# module_SX1278_A.net
KiCad netlist of a schematic drawn in EAGLE
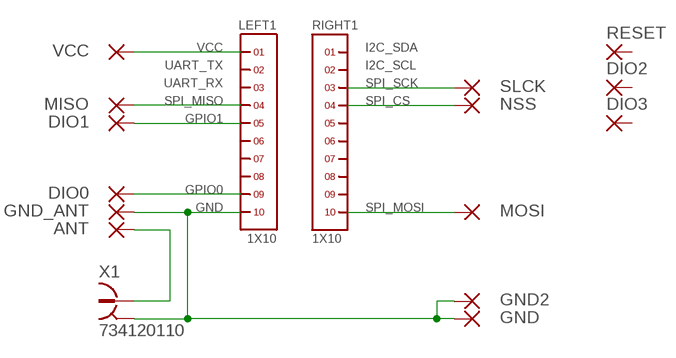
[diagram p0: schematic, sheet 1]

(export (version "E")
  (design (tool "Eeschema 10.0.6"))
  (components
    (comp (ref "ANT")
      (value "SMD1")
      (footprint "eagle-import:SMD0,65-1,27")
      (libsource (lib "eagle-import") (part "SMD1"))
    )
    (comp (ref "DIO0")
      (value "SMD1")
      (footprint "eagle-import:SMD0,65-1,27")
      (libsource (lib "eagle-import") (part "SMD1"))
    )
    (comp (ref "DIO1")
      (value "SMD1")
      (footprint "eagle-import:SMD0,65-1,27")
      (libsource (lib "eagle-import") (part "SMD1"))
    )
    (comp (ref "DIO2")
      (value "SMD1")
      (footprint "eagle-import:SMD0,65-1,27")
      (libsource (lib "eagle-import") (part "SMD1"))
    )
    (comp (ref "DIO3")
      (value "SMD1")
      (footprint "eagle-import:SMD0,65-1,27")
      (libsource (lib "eagle-import") (part "SMD1"))
    )
    (comp (ref "GND")
      (value "SMD1")
      (footprint "eagle-import:SMD0,65-1,27")
      (libsource (lib "eagle-import") (part "SMD1"))
    )
    (comp (ref "GND2")
      (value "SMD1")
      (footprint "eagle-import:SMD0,65-1,27")
      (libsource (lib "eagle-import") (part "SMD1"))
    )
    (comp (ref "GND_ANT")
      (value "SMD1")
      (footprint "eagle-import:SMD0,65-1,27")
      (libsource (lib "eagle-import") (part "SMD1"))
    )
    (comp (ref "LEFT1")
      (value "1X10")
      (footprint "eagle-import:1X10")
      (libsource (lib "eagle-import") (part "1X10"))
    )
    (comp (ref "MISO")
      (value "SMD1")
      (footprint "eagle-import:SMD0,65-1,27")
      (libsource (lib "eagle-import") (part "SMD1"))
    )
    (comp (ref "MOSI")
      (value "SMD1")
      (footprint "eagle-import:SMD0,65-1,27")
      (libsource (lib "eagle-import") (part "SMD1"))
    )
    (comp (ref "NSS")
      (value "SMD1")
      (footprint "eagle-import:SMD0,65-1,27")
      (libsource (lib "eagle-import") (part "SMD1"))
    )
    (comp (ref "RESET")
      (value "SMD1")
      (footprint "eagle-import:SMD0,65-1,27")
      (libsource (lib "eagle-import") (part "SMD1"))
    )
    (comp (ref "RIGHT1")
      (value "1X10")
      (footprint "eagle-import:1X10")
      (libsource (lib "eagle-import") (part "1X10"))
    )
    (comp (ref "SLCK")
      (value "SMD1")
      (footprint "eagle-import:SMD0,65-1,27")
      (libsource (lib "eagle-import") (part "SMD1"))
    )
    (comp (ref "VCC")
      (value "SMD1")
      (footprint "eagle-import:SMD0,65-1,27")
      (libsource (lib "eagle-import") (part "SMD1"))
    )
    (comp (ref "X1")
      (value "734120110")
      (footprint "eagle-import:734120110")
      (libsource (lib "eagle-import") (part "734120110"))
    )
  )
  (nets
    (net (code "1") (name "Net-(ANT-P)") (class "Default")
      (node (ref "ANT") (pin "1") (pinfunction "P_1") (pintype "passive"))
      (node (ref "X1") (pin "1") (pinfunction "1_1") (pintype "passive"))
    )
    (net (code "2") (name "Net-(DIO0-P)") (class "Default")
      (node (ref "DIO0") (pin "1") (pinfunction "P_1") (pintype "passive"))
      (node (ref "LEFT1") (pin "9") (pinfunction "9_9") (pintype "bidirectional"))
    )
    (net (code "3") (name "Net-(DIO1-P)") (class "Default")
      (node (ref "DIO1") (pin "1") (pinfunction "P_1") (pintype "passive"))
      (node (ref "LEFT1") (pin "5") (pinfunction "5_5") (pintype "bidirectional"))
    )
    (net (code "4") (name "Net-(GND-P)") (class "Default")
      (node (ref "GND") (pin "1") (pinfunction "P_1") (pintype "passive"))
      (node (ref "GND2") (pin "1") (pinfunction "P_1") (pintype "passive"))
      (node (ref "GND_ANT") (pin "1") (pinfunction "P_1") (pintype "passive"))
      (node (ref "LEFT1") (pin "10") (pinfunction "10_10") (pintype "bidirectional"))
      (node (ref "X1") (pin "S@1") (pinfunction "2_S@1") (pintype "passive"))
      (node (ref "X1") (pin "S@2") (pinfunction "2_S@2") (pintype "passive"))
      (node (ref "X1") (pin "S@3") (pinfunction "2_S@3") (pintype "passive"))
    )
    (net (code "5") (name "Net-(MISO-P)") (class "Default")
      (node (ref "LEFT1") (pin "4") (pinfunction "4_4") (pintype "bidirectional"))
      (node (ref "MISO") (pin "1") (pinfunction "P_1") (pintype "passive"))
    )
    (net (code "6") (name "Net-(MOSI-P)") (class "Default")
      (node (ref "MOSI") (pin "1") (pinfunction "P_1") (pintype "passive"))
      (node (ref "RIGHT1") (pin "10") (pinfunction "10_10") (pintype "bidirectional"))
    )
    (net (code "7") (name "Net-(NSS-P)") (class "Default")
      (node (ref "NSS") (pin "1") (pinfunction "P_1") (pintype "passive"))
      (node (ref "RIGHT1") (pin "4") (pinfunction "4_4") (pintype "bidirectional"))
    )
    (net (code "8") (name "Net-(SLCK-P)") (class "Default")
      (node (ref "RIGHT1") (pin "3") (pinfunction "3_3") (pintype "bidirectional"))
      (node (ref "SLCK") (pin "1") (pinfunction "P_1") (pintype "passive"))
    )
    (net (code "9") (name "Net-(VCC-P)") (class "Default")
      (node (ref "LEFT1") (pin "1") (pinfunction "1_1") (pintype "bidirectional"))
      (node (ref "VCC") (pin "1") (pinfunction "P_1") (pintype "passive"))
    )
    (net (code "10") (name "unconnected-(DIO2-P-Pad1)") (class "Default")
      (node (ref "DIO2") (pin "1") (pinfunction "P_1") (pintype "passive"))
    )
    (net (code "11") (name "unconnected-(DIO3-P-Pad1)") (class "Default")
      (node (ref "DIO3") (pin "1") (pinfunction "P_1") (pintype "passive"))
    )
    (net (code "12") (name "unconnected-(LEFT1-Pad2)") (class "Default")
      (node (ref "LEFT1") (pin "2") (pinfunction "2_2") (pintype "bidirectional"))
    )
    (net (code "13") (name "unconnected-(LEFT1-Pad3)") (class "Default")
      (node (ref "LEFT1") (pin "3") (pinfunction "3_3") (pintype "bidirectional"))
    )
    (net (code "14") (name "unconnected-(LEFT1-Pad6)") (class "Default")
      (node (ref "LEFT1") (pin "6") (pinfunction "6_6") (pintype "bidirectional"))
    )
    (net (code "15") (name "unconnected-(LEFT1-Pad7)") (class "Default")
      (node (ref "LEFT1") (pin "7") (pinfunction "7_7") (pintype "bidirectional"))
    )
    (net (code "16") (name "unconnected-(LEFT1-Pad8)") (class "Default")
      (node (ref "LEFT1") (pin "8") (pinfunction "8_8") (pintype "bidirectional"))
    )
    (net (code "17") (name "unconnected-(RESET-P-Pad1)") (class "Default")
      (node (ref "RESET") (pin "1") (pinfunction "P_1") (pintype "passive"))
    )
    (net (code "18") (name "unconnected-(RIGHT1-Pad1)") (class "Default")
      (node (ref "RIGHT1") (pin "1") (pinfunction "1_1") (pintype "bidirectional"))
    )
    (net (code "19") (name "unconnected-(RIGHT1-Pad2)") (class "Default")
      (node (ref "RIGHT1") (pin "2") (pinfunction "2_2") (pintype "bidirectional"))
    )
    (net (code "20") (name "unconnected-(RIGHT1-Pad5)") (class "Default")
      (node (ref "RIGHT1") (pin "5") (pinfunction "5_5") (pintype "bidirectional"))
    )
    (net (code "21") (name "unconnected-(RIGHT1-Pad6)") (class "Default")
      (node (ref "RIGHT1") (pin "6") (pinfunction "6_6") (pintype "bidirectional"))
    )
    (net (code "22") (name "unconnected-(RIGHT1-Pad7)") (class "Default")
      (node (ref "RIGHT1") (pin "7") (pinfunction "7_7") (pintype "bidirectional"))
    )
    (net (code "23") (name "unconnected-(RIGHT1-Pad8)") (class "Default")
      (node (ref "RIGHT1") (pin "8") (pinfunction "8_8") (pintype "bidirectional"))
    )
    (net (code "24") (name "unconnected-(RIGHT1-Pad9)") (class "Default")
      (node (ref "RIGHT1") (pin "9") (pinfunction "9_9") (pintype "bidirectional"))
    )
  )
)
